# frankfurt_eth_rev_A.net
KiCad netlist of a schematic drawn in EAGLE
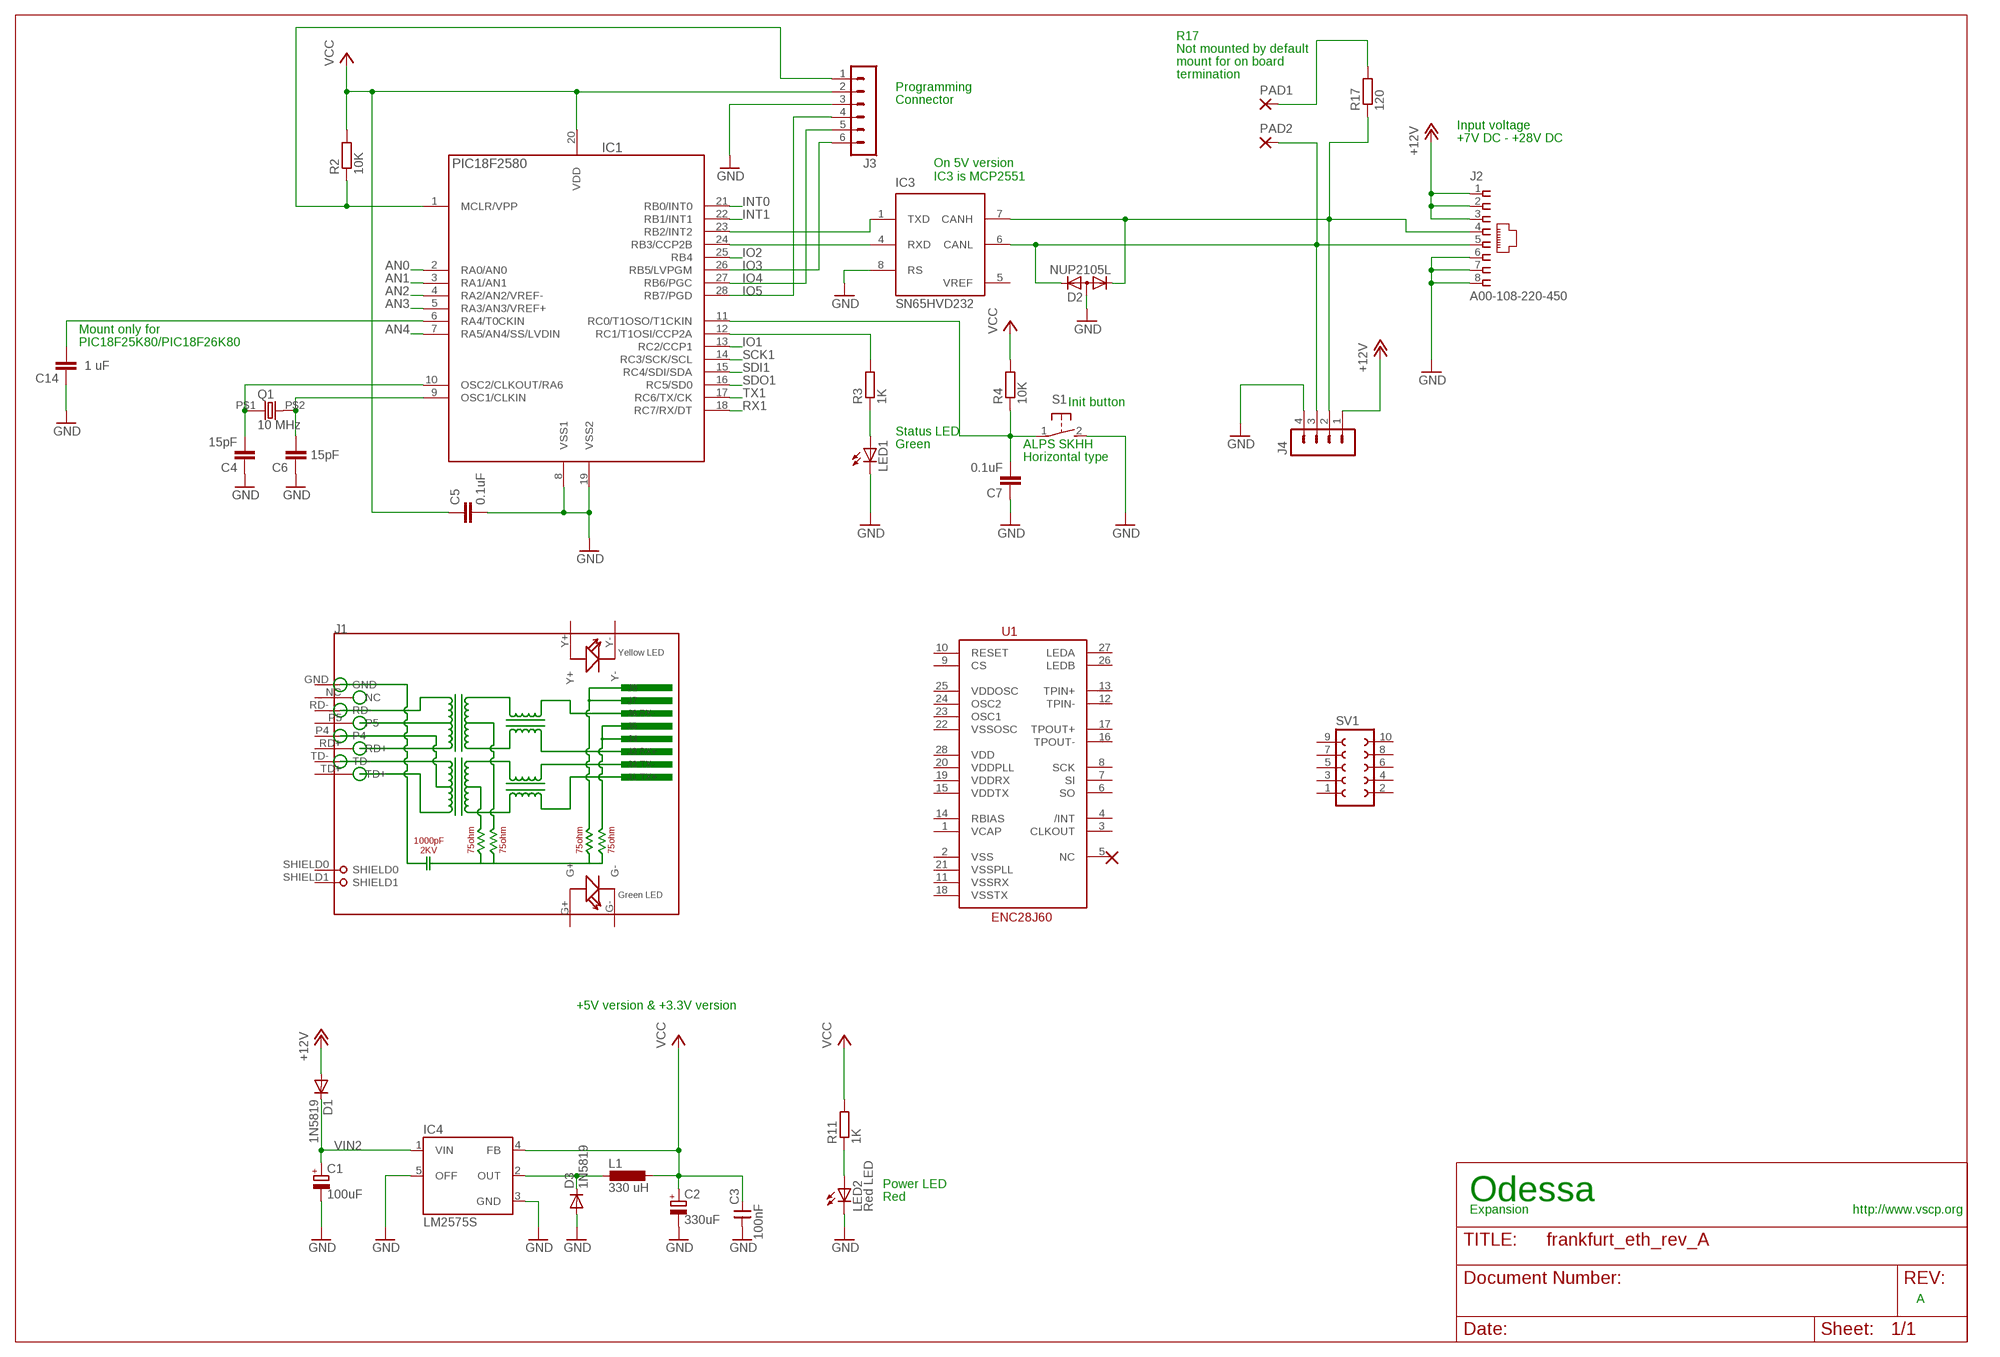
[diagram p0: schematic, sheet 1]

(export (version "E")
  (design (tool "Eeschema 10.0.6"))
  (components
    (comp (ref "C1")
      (value "100uF")
      (footprint "eagle-import:PANASONIC_D")
      (libsource (lib "eagle-import") (part "CPOL-EUD"))
    )
    (comp (ref "C2")
      (value "330uF")
      (footprint "eagle-import:PANASONIC_D")
      (libsource (lib "eagle-import") (part "CPOL-EUD"))
    )
    (comp (ref "C3")
      (value "100nF")
      (footprint "eagle-import:0805")
      (libsource (lib "eagle-import") (part "CNP-0805"))
    )
    (comp (ref "C4")
      (value "15pF")
      (footprint "eagle-import:C0805")
      (libsource (lib "eagle-import") (part "C-EUC0805"))
    )
    (comp (ref "C5")
      (value "0.1uF")
      (footprint "eagle-import:C0805")
      (libsource (lib "eagle-import") (part "C-EUC0805"))
    )
    (comp (ref "C6")
      (value "15pF")
      (footprint "eagle-import:C0805")
      (libsource (lib "eagle-import") (part "C-EUC0805"))
    )
    (comp (ref "C7")
      (value "0.1uF")
      (footprint "eagle-import:C0805")
      (libsource (lib "eagle-import") (part "C-EUC0805"))
    )
    (comp (ref "C14")
      (value "1 uF")
      (footprint "eagle-import:C0805")
      (libsource (lib "eagle-import") (part "C-EUC0805"))
    )
    (comp (ref "D1")
      (value "1N5819")
      (footprint "eagle-import:SOD123")
      (libsource (lib "eagle-import") (part "DIODE-SOD123"))
    )
    (comp (ref "D2")
      (value "NUP2105L")
      (footprint "eagle-import:SOT23")
      (libsource (lib "eagle-import") (part "DIODE-2CA|ACSOT23"))
    )
    (comp (ref "D3")
      (value "1N5819")
      (footprint "eagle-import:SOD123")
      (libsource (lib "eagle-import") (part "DIODE-SOD123"))
    )
    (comp (ref "IC1")
      (value "PIC18F2580")
      (footprint "eagle-import:SO28")
      (libsource (lib "eagle-import") (part "PIC18F252-?I/SOL"))
    )
    (comp (ref "IC3")
      (value "SN65HVD232")
      (footprint "eagle-import:SO-08")
      (libsource (lib "eagle-import") (part "MCP2551SN"))
    )
    (comp (ref "IC4")
      (value "LM2575S")
      (footprint "eagle-import:TO263-5")
      (libsource (lib "eagle-import") (part "LM2575S"))
    )
    (comp (ref "J1")
      (value "RJ45-HR911105A-HR911105A")
      (footprint "eagle-import:RJ45")
      (libsource (lib "eagle-import") (part "RJ45-HR911105A-HR911105A"))
    )
    (comp (ref "J2")
      (value "A00-108-220-450")
      (footprint "eagle-import:RJ-45")
      (libsource (lib "eagle-import") (part "A00-108-220-450"))
    )
    (comp (ref "J3")
      (value "MA06-1")
      (footprint "eagle-import:MA06-1")
      (libsource (lib "eagle-import") (part "MA06-1"))
    )
    (comp (ref "J4")
      (value "MA04-1")
      (footprint "eagle-import:MA04-1")
      (libsource (lib "eagle-import") (part "MA04-1"))
    )
    (comp (ref "L1")
      (value "330 uH")
      (footprint "eagle-import:DO3316P")
      (libsource (lib "eagle-import") (part "DO3316P"))
    )
    (comp (ref "LED1")
      (value "LEDCHIP-LED0805")
      (footprint "eagle-import:CHIP-LED0805")
      (libsource (lib "eagle-import") (part "LEDCHIP-LED0805"))
    )
    (comp (ref "LED2")
      (value "Red LED")
      (footprint "eagle-import:CHIP-LED0805")
      (libsource (lib "eagle-import") (part "LEDCHIP-LED0805"))
    )
    (comp (ref "PAD1")
      (value "1,6/0,8")
      (footprint "eagle-import:1,6_0,8")
      (libsource (lib "eagle-import") (part "1,6/0,8"))
    )
    (comp (ref "PAD2")
      (value "1,6/0,8")
      (footprint "eagle-import:1,6_0,8")
      (libsource (lib "eagle-import") (part "1,6/0,8"))
    )
    (comp (ref "Q1")
      (value "10 MHz")
      (footprint "eagle-import:9C")
      (libsource (lib "eagle-import") (part "HC-49S"))
    )
    (comp (ref "R2")
      (value "10K")
      (footprint "eagle-import:R0805")
      (libsource (lib "eagle-import") (part "R-EU_R0805"))
    )
    (comp (ref "R3")
      (value "1K")
      (footprint "eagle-import:R0805")
      (libsource (lib "eagle-import") (part "R-EU_R0805"))
    )
    (comp (ref "R4")
      (value "10K")
      (footprint "eagle-import:R0805")
      (libsource (lib "eagle-import") (part "R-EU_R0805"))
    )
    (comp (ref "R11")
      (value "1K")
      (footprint "eagle-import:R0805")
      (libsource (lib "eagle-import") (part "R-EU_R0805"))
    )
    (comp (ref "R17")
      (value "120")
      (footprint "eagle-import:R0805")
      (libsource (lib "eagle-import") (part "R-EU_R0805"))
    )
    (comp (ref "S1")
      (value "31-XX")
      (footprint "eagle-import:B3F-31XX")
      (fields (field (name "MPN") "B3F-3100"))
      (libsource (lib "eagle-import") (part "31-XX"))
    )
    (comp (ref "SV1")
      (value "FE05-2")
      (footprint "eagle-import:FE05-2")
      (libsource (lib "eagle-import") (part "FE05-2"))
    )
    (comp (ref "U1")
      (value "ENC28J60")
      (footprint "eagle-import:SSOP28DB")
      (libsource (lib "eagle-import") (part "ENC28J60"))
    )
  )
  (nets
    (net (code "1") (name "+12V") (class "Default")
      (node (ref "D1") (pin "A") (pinfunction "A_A") (pintype "passive"))
      (node (ref "J2") (pin "1") (pinfunction "1_1") (pintype "passive"))
      (node (ref "J2") (pin "2") (pinfunction "2_2") (pintype "passive"))
      (node (ref "J2") (pin "3") (pinfunction "3_3") (pintype "passive"))
      (node (ref "J4") (pin "1") (pinfunction "1_1") (pintype "passive"))
    )
    (net (code "2") (name "/AN0") (class "Default")
      (node (ref "IC1") (pin "2") (pinfunction "RA0/AN0_2") (pintype "bidirectional"))
    )
    (net (code "3") (name "/AN1") (class "Default")
      (node (ref "IC1") (pin "3") (pinfunction "RA1/AN1_3") (pintype "bidirectional"))
    )
    (net (code "4") (name "/AN2") (class "Default")
      (node (ref "IC1") (pin "4") (pinfunction "RA2/AN2/VREF-_4") (pintype "bidirectional"))
    )
    (net (code "5") (name "/AN3") (class "Default")
      (node (ref "IC1") (pin "5") (pinfunction "RA3/AN3/VREF+_5") (pintype "bidirectional"))
    )
    (net (code "6") (name "/AN4") (class "Default")
      (node (ref "IC1") (pin "7") (pinfunction "RA5/AN4/SS/LVDIN_7") (pintype "bidirectional"))
    )
    (net (code "7") (name "/INT0") (class "Default")
      (node (ref "IC1") (pin "21") (pinfunction "RB0/INT0_21") (pintype "bidirectional"))
    )
    (net (code "8") (name "/INT1") (class "Default")
      (node (ref "IC1") (pin "22") (pinfunction "RB1/INT1_22") (pintype "bidirectional"))
    )
    (net (code "9") (name "/IO1") (class "Default")
      (node (ref "IC1") (pin "13") (pinfunction "RC2/CCP1_13") (pintype "bidirectional"))
    )
    (net (code "10") (name "/IO2") (class "Default")
      (node (ref "IC1") (pin "25") (pinfunction "RB4_25") (pintype "bidirectional"))
    )
    (net (code "11") (name "/IO3") (class "Default")
      (node (ref "IC1") (pin "26") (pinfunction "RB5/LVPGM_26") (pintype "bidirectional"))
      (node (ref "J3") (pin "6") (pinfunction "6_6") (pintype "passive"))
    )
    (net (code "12") (name "/IO4") (class "Default")
      (node (ref "IC1") (pin "27") (pinfunction "RB6/PGC_27") (pintype "bidirectional"))
      (node (ref "J3") (pin "5") (pinfunction "5_5") (pintype "passive"))
    )
    (net (code "13") (name "/IO5") (class "Default")
      (node (ref "IC1") (pin "28") (pinfunction "RB7/PGD_28") (pintype "bidirectional"))
      (node (ref "J3") (pin "4") (pinfunction "4_4") (pintype "passive"))
    )
    (net (code "14") (name "/RX1") (class "Default")
      (node (ref "IC1") (pin "18") (pinfunction "RC7/RX/DT_18") (pintype "bidirectional"))
    )
    (net (code "15") (name "/SCK1") (class "Default")
      (node (ref "IC1") (pin "14") (pinfunction "RC3/SCK/SCL_14") (pintype "bidirectional"))
    )
    (net (code "16") (name "/SDI1") (class "Default")
      (node (ref "IC1") (pin "15") (pinfunction "RC4/SDI/SDA_15") (pintype "bidirectional"))
    )
    (net (code "17") (name "/SDO1") (class "Default")
      (node (ref "IC1") (pin "16") (pinfunction "RC5/SD0_16") (pintype "bidirectional"))
    )
    (net (code "18") (name "/TX1") (class "Default")
      (node (ref "IC1") (pin "17") (pinfunction "RC6/TX/CK_17") (pintype "bidirectional"))
    )
    (net (code "19") (name "/VIN2") (class "Default")
      (node (ref "C1") (pin "+") (pinfunction "+_+") (pintype "passive"))
      (node (ref "D1") (pin "C") (pinfunction "C_C") (pintype "passive"))
      (node (ref "IC4") (pin "1") (pinfunction "VIN_1") (pintype "power_in"))
    )
    (net (code "20") (name "/VREF") (class "Default")
      (node (ref "IC3") (pin "5") (pinfunction "VREF_5") (pintype "power_in"))
    )
    (net (code "21") (name "GND") (class "Default")
      (node (ref "C1") (pin "-") (pinfunction "-_-") (pintype "passive"))
      (node (ref "C14") (pin "1") (pinfunction "1_1") (pintype "passive"))
      (node (ref "C2") (pin "-") (pinfunction "-_-") (pintype "passive"))
      (node (ref "C3") (pin "1") (pinfunction "1_1") (pintype "passive"))
      (node (ref "C4") (pin "1") (pinfunction "1_1") (pintype "passive"))
      (node (ref "C5") (pin "2") (pinfunction "2_2") (pintype "passive"))
      (node (ref "C6") (pin "1") (pinfunction "1_1") (pintype "passive"))
      (node (ref "C7") (pin "1") (pinfunction "1_1") (pintype "passive"))
      (node (ref "D2") (pin "3") (pinfunction "A_3") (pintype "passive"))
      (node (ref "D3") (pin "A") (pinfunction "A_A") (pintype "passive"))
      (node (ref "IC1") (pin "19") (pinfunction "VSS2_19") (pintype "power_in"))
      (node (ref "IC1") (pin "8") (pinfunction "VSS1_8") (pintype "power_in"))
      (node (ref "IC3") (pin "8") (pinfunction "RS_8") (pintype "input"))
      (node (ref "IC4") (pin "3") (pinfunction "GND_3") (pintype "power_in"))
      (node (ref "IC4") (pin "5") (pinfunction "OFF_5") (pintype "input"))
      (node (ref "J2") (pin "6") (pinfunction "6_6") (pintype "passive"))
      (node (ref "J2") (pin "7") (pinfunction "7_7") (pintype "passive"))
      (node (ref "J2") (pin "8") (pinfunction "8_8") (pintype "passive"))
      (node (ref "J3") (pin "3") (pinfunction "3_3") (pintype "passive"))
      (node (ref "J4") (pin "4") (pinfunction "4_4") (pintype "passive"))
      (node (ref "LED1") (pin "C") (pinfunction "C_C") (pintype "passive"))
      (node (ref "LED2") (pin "C") (pinfunction "C_C") (pintype "passive"))
      (node (ref "S1") (pin "2") (pinfunction "S_2") (pintype "passive"))
    )
    (net (code "22") (name "Net-(D2-K1)") (class "Default")
      (node (ref "D2") (pin "1") (pinfunction "K1_1") (pintype "passive"))
      (node (ref "IC3") (pin "7") (pinfunction "CANH_7") (pintype "bidirectional"))
      (node (ref "J2") (pin "4") (pinfunction "4_4") (pintype "passive"))
      (node (ref "J4") (pin "2") (pinfunction "2_2") (pintype "passive"))
      (node (ref "R17") (pin "1") (pinfunction "1_1") (pintype "passive"))
    )
    (net (code "23") (name "Net-(D2-K2)") (class "Default")
      (node (ref "D2") (pin "2") (pinfunction "K2_2") (pintype "passive"))
      (node (ref "IC3") (pin "6") (pinfunction "CANL_6") (pintype "bidirectional"))
      (node (ref "J2") (pin "5") (pinfunction "5_5") (pintype "passive"))
      (node (ref "J4") (pin "3") (pinfunction "3_3") (pintype "passive"))
      (node (ref "PAD2") (pin "1") (pinfunction "P_1") (pintype "passive"))
    )
    (net (code "24") (name "Net-(IC1-MCLR{slash}VPP)") (class "Default")
      (node (ref "IC1") (pin "1") (pinfunction "MCLR/VPP_1") (pintype "input"))
      (node (ref "J3") (pin "1") (pinfunction "1_1") (pintype "passive"))
      (node (ref "R2") (pin "1") (pinfunction "1_1") (pintype "passive"))
    )
    (net (code "25") (name "Net-(IC1-OSC1{slash}CLKIN)") (class "Default")
      (node (ref "C6") (pin "2") (pinfunction "2_2") (pintype "passive"))
      (node (ref "IC1") (pin "9") (pinfunction "OSC1/CLKIN_9") (pintype "input"))
      (node (ref "Q1") (pin "P$2") (pinfunction "2_P$2") (pintype "passive"))
    )
    (net (code "26") (name "Net-(IC1-OSC2{slash}CLKOUT{slash}RA6)") (class "Default")
      (node (ref "C4") (pin "2") (pinfunction "2_2") (pintype "passive"))
      (node (ref "IC1") (pin "10") (pinfunction "OSC2/CLKOUT/RA6_10") (pintype "output"))
      (node (ref "Q1") (pin "P$1") (pinfunction "1_P$1") (pintype "passive"))
    )
    (net (code "27") (name "Net-(IC1-RA4{slash}T0CKIN)") (class "Default")
      (node (ref "C14") (pin "2") (pinfunction "2_2") (pintype "passive"))
      (node (ref "IC1") (pin "6") (pinfunction "RA4/T0CKIN_6") (pintype "open_collector"))
    )
    (net (code "28") (name "Net-(IC1-RB2{slash}INT2)") (class "Default")
      (node (ref "IC1") (pin "23") (pinfunction "RB2/INT2_23") (pintype "bidirectional"))
      (node (ref "IC3") (pin "1") (pinfunction "TXD_1") (pintype "input"))
    )
    (net (code "29") (name "Net-(IC1-RB3{slash}CCP2B)") (class "Default")
      (node (ref "IC1") (pin "24") (pinfunction "RB3/CCP2B_24") (pintype "bidirectional"))
      (node (ref "IC3") (pin "4") (pinfunction "RXD_4") (pintype "output"))
    )
    (net (code "30") (name "Net-(IC1-RC0{slash}T1OSO{slash}T1CKIN)") (class "Default")
      (node (ref "C7") (pin "2") (pinfunction "2_2") (pintype "passive"))
      (node (ref "IC1") (pin "11") (pinfunction "RC0/T1OSO/T1CKIN_11") (pintype "bidirectional"))
      (node (ref "R4") (pin "1") (pinfunction "1_1") (pintype "passive"))
      (node (ref "S1") (pin "1") (pinfunction "P_1") (pintype "passive"))
    )
    (net (code "31") (name "Net-(IC1-RC1{slash}T1OSI{slash}CCP2A)") (class "Default")
      (node (ref "IC1") (pin "12") (pinfunction "RC1/T1OSI/CCP2A_12") (pintype "bidirectional"))
      (node (ref "R3") (pin "2") (pinfunction "2_2") (pintype "passive"))
    )
    (net (code "32") (name "Net-(IC4-OUT)") (class "Default")
      (node (ref "D3") (pin "C") (pinfunction "C_C") (pintype "passive"))
      (node (ref "IC4") (pin "2") (pinfunction "OUT_2") (pintype "output"))
      (node (ref "L1") (pin "1") (pinfunction "1_1") (pintype "passive"))
    )
    (net (code "33") (name "Net-(LED1-PadA)") (class "Default")
      (node (ref "LED1") (pin "A") (pinfunction "A_A") (pintype "passive"))
      (node (ref "R3") (pin "1") (pinfunction "1_1") (pintype "passive"))
    )
    (net (code "34") (name "Net-(LED2-PadA)") (class "Default")
      (node (ref "LED2") (pin "A") (pinfunction "A_A") (pintype "passive"))
      (node (ref "R11") (pin "1") (pinfunction "1_1") (pintype "passive"))
    )
    (net (code "35") (name "Net-(PAD1-P)") (class "Default")
      (node (ref "PAD1") (pin "1") (pinfunction "P_1") (pintype "passive"))
      (node (ref "R17") (pin "2") (pinfunction "2_2") (pintype "passive"))
    )
    (net (code "36") (name "VCC") (class "Default")
      (node (ref "C2") (pin "+") (pinfunction "+_+") (pintype "passive"))
      (node (ref "C3") (pin "2") (pinfunction "2_2") (pintype "passive"))
      (node (ref "C5") (pin "1") (pinfunction "1_1") (pintype "passive"))
      (node (ref "IC1") (pin "20") (pinfunction "VDD_20") (pintype "power_in"))
      (node (ref "IC4") (pin "4") (pinfunction "FB_4") (pintype "input"))
      (node (ref "J3") (pin "2") (pinfunction "2_2") (pintype "passive"))
      (node (ref "L1") (pin "2") (pinfunction "2_2") (pintype "passive"))
      (node (ref "R11") (pin "2") (pinfunction "2_2") (pintype "passive"))
      (node (ref "R2") (pin "2") (pinfunction "2_2") (pintype "passive"))
      (node (ref "R4") (pin "2") (pinfunction "2_2") (pintype "passive"))
    )
    (net (code "37") (name "unconnected-(J1-PadG+)") (class "Default")
      (node (ref "J1") (pin "G+") (pinfunction "G+_G+") (pintype "bidirectional"))
    )
    (net (code "38") (name "unconnected-(J1-PadG-)") (class "Default")
      (node (ref "J1") (pin "G-") (pinfunction "G-_G-") (pintype "bidirectional"))
    )
    (net (code "39") (name "unconnected-(J1-PadGND)") (class "Default")
      (node (ref "J1") (pin "GND") (pinfunction "GND_GND") (pintype "bidirectional"))
    )
    (net (code "40") (name "unconnected-(J1-PadNC)") (class "Default")
      (node (ref "J1") (pin "NC") (pinfunction "NC_NC") (pintype "bidirectional"))
    )
    (net (code "41") (name "unconnected-(J1-PadP4)") (class "Default")
      (node (ref "J1") (pin "P4") (pinfunction "P4_P4") (pintype "bidirectional"))
    )
    (net (code "42") (name "unconnected-(J1-PadP5)") (class "Default")
      (node (ref "J1") (pin "P5") (pinfunction "P5_P5") (pintype "bidirectional"))
    )
    (net (code "43") (name "unconnected-(J1-PadRD+)") (class "Default")
      (node (ref "J1") (pin "RD+") (pinfunction "RD+_RD+") (pintype "bidirectional"))
    )
    (net (code "44") (name "unconnected-(J1-PadRD-)") (class "Default")
      (node (ref "J1") (pin "RD-") (pinfunction "RD-_RD-") (pintype "bidirectional"))
    )
    (net (code "45") (name "unconnected-(J1-PadSHIELD0)") (class "Default")
      (node (ref "J1") (pin "SHIELD0") (pinfunction "SHIELD0_SHIELD0") (pintype "bidirectional"))
    )
    (net (code "46") (name "unconnected-(J1-PadSHIELD1)") (class "Default")
      (node (ref "J1") (pin "SHIELD1") (pinfunction "SHIELD1_SHIELD1") (pintype "bidirectional"))
    )
    (net (code "47") (name "unconnected-(J1-PadTD+)") (class "Default")
      (node (ref "J1") (pin "TD+") (pinfunction "TD+_TD+") (pintype "bidirectional"))
    )
    (net (code "48") (name "unconnected-(J1-PadTD-)") (class "Default")
      (node (ref "J1") (pin "TD-") (pinfunction "TD-_TD-") (pintype "bidirectional"))
    )
    (net (code "49") (name "unconnected-(J1-PadY+)") (class "Default")
      (node (ref "J1") (pin "Y+") (pinfunction "Y+_Y+") (pintype "bidirectional"))
    )
    (net (code "50") (name "unconnected-(J1-PadY-)") (class "Default")
      (node (ref "J1") (pin "Y-") (pinfunction "Y-_Y-") (pintype "bidirectional"))
    )
    (net (code "51") (name "unconnected-(SV1-Pad1)") (class "Default")
      (node (ref "SV1") (pin "1") (pinfunction "1_1") (pintype "passive"))
    )
    (net (code "52") (name "unconnected-(SV1-Pad2)") (class "Default")
      (node (ref "SV1") (pin "2") (pinfunction "2_2") (pintype "passive"))
    )
    (net (code "53") (name "unconnected-(SV1-Pad3)") (class "Default")
      (node (ref "SV1") (pin "3") (pinfunction "3_3") (pintype "passive"))
    )
    (net (code "54") (name "unconnected-(SV1-Pad4)") (class "Default")
      (node (ref "SV1") (pin "4") (pinfunction "4_4") (pintype "passive"))
    )
    (net (code "55") (name "unconnected-(SV1-Pad5)") (class "Default")
      (node (ref "SV1") (pin "5") (pinfunction "5_5") (pintype "passive"))
    )
    (net (code "56") (name "unconnected-(SV1-Pad6)") (class "Default")
      (node (ref "SV1") (pin "6") (pinfunction "6_6") (pintype "passive"))
    )
    (net (code "57") (name "unconnected-(SV1-Pad7)") (class "Default")
      (node (ref "SV1") (pin "7") (pinfunction "7_7") (pintype "passive"))
    )
    (net (code "58") (name "unconnected-(SV1-Pad8)") (class "Default")
      (node (ref "SV1") (pin "8") (pinfunction "8_8") (pintype "passive"))
    )
    (net (code "59") (name "unconnected-(SV1-Pad9)") (class "Default")
      (node (ref "SV1") (pin "9") (pinfunction "9_9") (pintype "passive"))
    )
    (net (code "60") (name "unconnected-(SV1-Pad10)") (class "Default")
      (node (ref "SV1") (pin "10") (pinfunction "10_10") (pintype "passive"))
    )
    (net (code "61") (name "unconnected-(U1-CLKOUT-Pad3)") (class "Default")
      (node (ref "U1") (pin "3") (pinfunction "CLKOUT_3") (pintype "bidirectional"))
    )
    (net (code "62") (name "unconnected-(U1-CS-Pad9)") (class "Default")
      (node (ref "U1") (pin "9") (pinfunction "CS_9") (pintype "bidirectional"))
    )
    (net (code "63") (name "unconnected-(U1-LEDA-Pad27)") (class "Default")
      (node (ref "U1") (pin "27") (pinfunction "LEDA_27") (pintype "bidirectional"))
    )
    (net (code "64") (name "unconnected-(U1-LEDB-Pad26)") (class "Default")
      (node (ref "U1") (pin "26") (pinfunction "LEDB_26") (pintype "bidirectional"))
    )
    (net (code "65") (name "unconnected-(U1-NC-Pad5)") (class "Default")
      (node (ref "U1") (pin "5") (pinfunction "NC_5") (pintype "bidirectional"))
    )
    (net (code "66") (name "unconnected-(U1-OSC1-Pad23)") (class "Default")
      (node (ref "U1") (pin "23") (pinfunction "OSC1_23") (pintype "bidirectional"))
    )
    (net (code "67") (name "unconnected-(U1-OSC2-Pad24)") (class "Default")
      (node (ref "U1") (pin "24") (pinfunction "OSC2_24") (pintype "bidirectional"))
    )
    (net (code "68") (name "unconnected-(U1-RBIAS-Pad14)") (class "Default")
      (node (ref "U1") (pin "14") (pinfunction "RBIAS_14") (pintype "bidirectional"))
    )
    (net (code "69") (name "unconnected-(U1-RESET-Pad10)") (class "Default")
      (node (ref "U1") (pin "10") (pinfunction "RESET_10") (pintype "bidirectional"))
    )
    (net (code "70") (name "unconnected-(U1-SCK-Pad8)") (class "Default")
      (node (ref "U1") (pin "8") (pinfunction "SCK_8") (pintype "bidirectional"))
    )
    (net (code "71") (name "unconnected-(U1-SI-Pad7)") (class "Default")
      (node (ref "U1") (pin "7") (pinfunction "SI_7") (pintype "bidirectional"))
    )
    (net (code "72") (name "unconnected-(U1-SO-Pad6)") (class "Default")
      (node (ref "U1") (pin "6") (pinfunction "SO_6") (pintype "bidirectional"))
    )
    (net (code "73") (name "unconnected-(U1-TPIN+-Pad13)") (class "Default")
      (node (ref "U1") (pin "13") (pinfunction "TPIN+_13") (pintype "bidirectional"))
    )
    (net (code "74") (name "unconnected-(U1-TPIN--Pad12)") (class "Default")
      (node (ref "U1") (pin "12") (pinfunction "TPIN-_12") (pintype "bidirectional"))
    )
    (net (code "75") (name "unconnected-(U1-TPOUT+-Pad17)") (class "Default")
      (node (ref "U1") (pin "17") (pinfunction "TPOUT+_17") (pintype "bidirectional"))
    )
    (net (code "76") (name "unconnected-(U1-TPOUT--Pad16)") (class "Default")
      (node (ref "U1") (pin "16") (pinfunction "TPOUT-_16") (pintype "bidirectional"))
    )
    (net (code "77") (name "unconnected-(U1-VCAP-Pad1)") (class "Default")
      (node (ref "U1") (pin "1") (pinfunction "VCAP_1") (pintype "bidirectional"))
    )
    (net (code "78") (name "unconnected-(U1-VDD-Pad28)") (class "Default")
      (node (ref "U1") (pin "28") (pinfunction "VDD_28") (pintype "bidirectional"))
    )
    (net (code "79") (name "unconnected-(U1-VDDOSC-Pad25)") (class "Default")
      (node (ref "U1") (pin "25") (pinfunction "VDDOSC_25") (pintype "bidirectional"))
    )
    (net (code "80") (name "unconnected-(U1-VDDPLL-Pad20)") (class "Default")
      (node (ref "U1") (pin "20") (pinfunction "VDDPLL_20") (pintype "bidirectional"))
    )
    (net (code "81") (name "unconnected-(U1-VDDRX-Pad19)") (class "Default")
      (node (ref "U1") (pin "19") (pinfunction "VDDRX_19") (pintype "bidirectional"))
    )
    (net (code "82") (name "unconnected-(U1-VDDTX-Pad15)") (class "Default")
      (node (ref "U1") (pin "15") (pinfunction "VDDTX_15") (pintype "bidirectional"))
    )
    (net (code "83") (name "unconnected-(U1-VSS-Pad2)") (class "Default")
      (node (ref "U1") (pin "2") (pinfunction "VSS_2") (pintype "bidirectional"))
    )
    (net (code "84") (name "unconnected-(U1-VSSOSC-Pad22)") (class "Default")
      (node (ref "U1") (pin "22") (pinfunction "VSSOSC_22") (pintype "bidirectional"))
    )
    (net (code "85") (name "unconnected-(U1-VSSPLL-Pad21)") (class "Default")
      (node (ref "U1") (pin "21") (pinfunction "VSSPLL_21") (pintype "bidirectional"))
    )
    (net (code "86") (name "unconnected-(U1-VSSRX-Pad11)") (class "Default")
      (node (ref "U1") (pin "11") (pinfunction "VSSRX_11") (pintype "bidirectional"))
    )
    (net (code "87") (name "unconnected-(U1-VSSTX-Pad18)") (class "Default")
      (node (ref "U1") (pin "18") (pinfunction "VSSTX_18") (pintype "bidirectional"))
    )
    (net (code "88") (name "unconnected-(U1-{slash}INT-Pad4)") (class "Default")
      (node (ref "U1") (pin "4") (pinfunction "/INT_4") (pintype "bidirectional"))
    )
  )
)
